# SensorBoard.net
KiCad netlist of a schematic drawn in Altium Designer
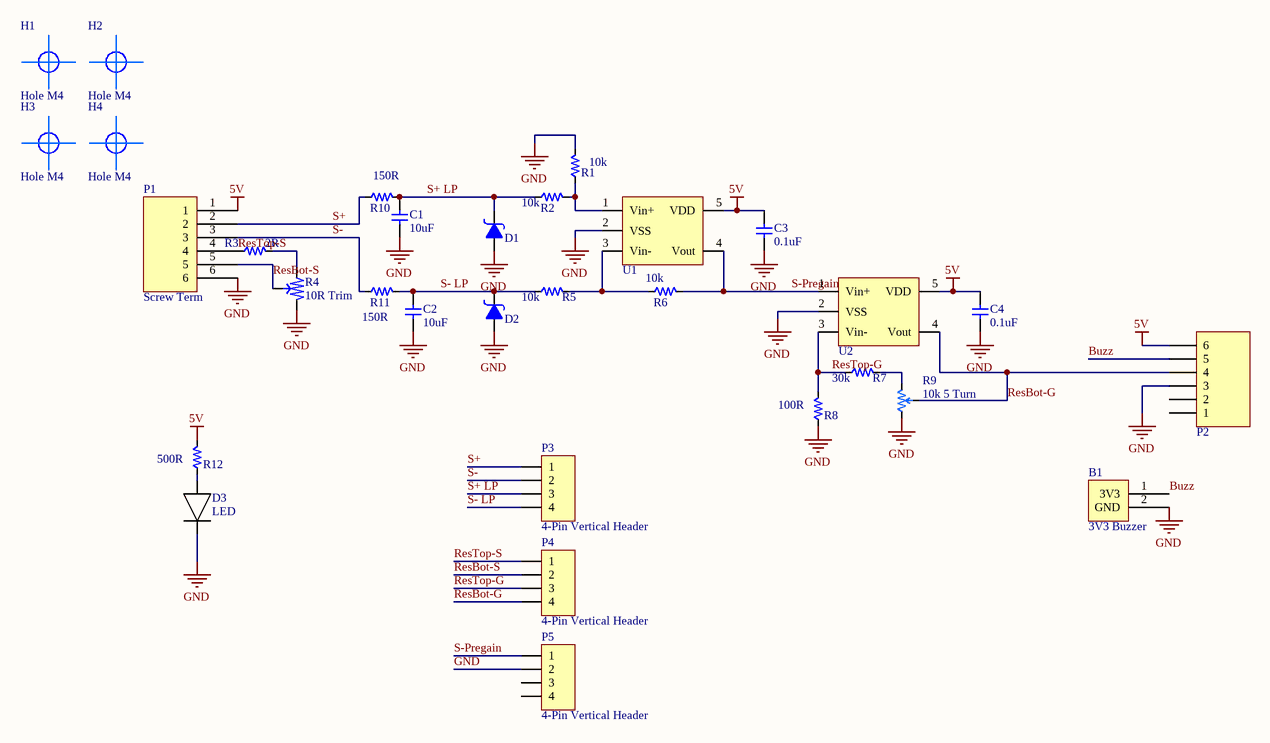
[diagram p0: SensorBoard.SchDoc]

(export (version "E")
  (design (tool "Eeschema 10.0.6"))
  (components
    (comp (ref "B1")
      (value "3V3 Buzzer")
      (footprint "Buzzer_surfacemount")
      (description "AUDIO PIEZO INDICATOR 2-5V TH")
      (libsource (lib "Buzzer_surfacemount") (part "Buzzer_surfacemount"))
    )
    (comp (ref "C1")
      (value "10uF")
      (footprint "PCB_GENERIC_SMD_0603")
      (description "CAP CER 0603 1uF 16V X5R 20%")
      (fields (field (name "TOLERANCE") "20%") (field (name "VOLTAGE") "16V"))
      (libsource (lib "CAP-0603") (part "C060-0001U-00"))
    )
    (comp (ref "C2")
      (value "10uF")
      (footprint "PCB_GENERIC_SMD_0603")
      (description "CAP CER 0603 1uF 16V X5R 20%")
      (fields (field (name "TOLERANCE") "20%") (field (name "VOLTAGE") "16V"))
      (libsource (lib "CAP-0603") (part "C060-0001U-00"))
    )
    (comp (ref "C3")
      (value "0.1uF")
      (footprint "PCB_GENERIC_SMD_0603")
      (description "CAP CER 0603 1uF 16V X5R 20%")
      (fields (field (name "TOLERANCE") "20%") (field (name "VOLTAGE") "16V"))
      (libsource (lib "CAP-0603") (part "C060-0001U-00"))
    )
    (comp (ref "C4")
      (value "0.1uF")
      (footprint "PCB_GENERIC_SMD_0603")
      (description "CAP CER 0603 1uF 16V X5R 20%")
      (fields (field (name "TOLERANCE") "20%") (field (name "VOLTAGE") "16V"))
      (libsource (lib "CAP-0603") (part "C060-0001U-00"))
    )
    (comp (ref "D1")
      (value "ONSEMI_MBRM110LT1G")
      (footprint "ON Semi Schottky Diode - MBRM110LT1G")
      (description "DIODE SCHOTTKY 10V 1A")
      (libsource (lib "ON Semi Schottky Diode") (part "ONSEMI_MBRM110LT1G"))
    )
    (comp (ref "D2")
      (value "ONSEMI_MBRM110LT1G")
      (footprint "ON Semi Schottky Diode - MBRM110LT1G")
      (description "DIODE SCHOTTKY 10V 1A")
      (libsource (lib "ON Semi Schottky Diode") (part "ONSEMI_MBRM110LT1G"))
    )
    (comp (ref "D3")
      (value "LED")
      (footprint "SMD_0603_LED")
      (libsource (lib "0603 LED") (part "SMD_0603_LED"))
    )
    (comp (ref "H1") (value "Hole M4") (footprint "M4_Hole") (libsource (lib "M4") (part "Component_1")))
    (comp (ref "H2") (value "Hole M4") (footprint "M4_Hole") (libsource (lib "M4") (part "Component_1")))
    (comp (ref "H3") (value "Hole M4") (footprint "M4_Hole") (libsource (lib "M4") (part "Component_1")))
    (comp (ref "H4") (value "Hole M4") (footprint "M4_Hole") (libsource (lib "M4") (part "Component_1")))
    (comp (ref "P1")
      (value "Screw Term")
      (footprint "6_Pin_ScrewTerm")
      (description "CONN TERM BLOCK 6POS 5MM BLACK")
      (libsource (lib "6_Pin_ScrewTerm") (part "Component_1"))
    )
    (comp (ref "P2")
      (value "SCH_MLX_MICROFIT_3X2")
      (footprint "PCB_MLX_MICROFIT_3X2")
      (libsource (lib "Molex Microfit 3.0 3x2") (part "SCH_MLX_MICROFIT_3X2"))
    )
    (comp (ref "P3")
      (value "4-Pin Vertical Header")
      (footprint "4-Pin Vertical Header")
      (fields (field (name "MANUFACTURER") "Sullins"))
      (libsource (lib "4 Pin 100 mil Vertical Header - Through Hole") (part "4-Pin Vertical Header"))
    )
    (comp (ref "P4")
      (value "4-Pin Vertical Header")
      (footprint "4-Pin Vertical Header")
      (fields (field (name "MANUFACTURER") "Sullins"))
      (libsource (lib "4 Pin 100 mil Vertical Header - Through Hole") (part "4-Pin Vertical Header"))
    )
    (comp (ref "P5")
      (value "4-Pin Vertical Header")
      (footprint "4-Pin Vertical Header")
      (fields (field (name "MANUFACTURER") "Sullins"))
      (libsource (lib "4 Pin 100 mil Vertical Header - Through Hole") (part "4-Pin Vertical Header"))
    )
    (comp (ref "R1")
      (value "SCH_GENERIC_RESISTOR_0603")
      (footprint "PCB_GENERIC_SMD_0603")
      (description "Generic SMD resistor 0603")
      (fields (field (name "RESISTANCE") "10k"))
      (libsource (lib "Generic 0603 Resistor") (part "SCH_GENERIC_RESISTOR_0603"))
    )
    (comp (ref "R2")
      (value "SCH_GENERIC_RESISTOR_0603")
      (footprint "PCB_GENERIC_SMD_0603")
      (description "Generic SMD resistor 0603")
      (fields (field (name "RESISTANCE") "10k"))
      (libsource (lib "Generic 0603 Resistor") (part "SCH_GENERIC_RESISTOR_0603"))
    )
    (comp (ref "R3")
      (value "SCH_GENERIC_RESISTOR_0603")
      (footprint "PCB_GENERIC_SMD_0603")
      (description "Generic SMD resistor 0603")
      (fields (field (name "RESISTANCE") "2R"))
      (libsource (lib "Generic 0603 Resistor") (part "SCH_GENERIC_RESISTOR_0603"))
    )
    (comp (ref "R4")
      (value "10R Trim")
      (footprint "10ohm1Turn_pot")
      (description "TRIMMER 10 OHM 0.25W SMD")
      (libsource (lib "10ohm1Turn_pot") (part "10ohm1Turn_pot"))
    )
    (comp (ref "R5")
      (value "SCH_GENERIC_RESISTOR_0603")
      (footprint "PCB_GENERIC_SMD_0603")
      (description "Generic SMD resistor 0603")
      (fields (field (name "RESISTANCE") "10k"))
      (libsource (lib "Generic 0603 Resistor") (part "SCH_GENERIC_RESISTOR_0603"))
    )
    (comp (ref "R6")
      (value "SCH_GENERIC_RESISTOR_0603")
      (footprint "PCB_GENERIC_SMD_0603")
      (description "Generic SMD resistor 0603")
      (fields (field (name "RESISTANCE") "10k"))
      (libsource (lib "Generic 0603 Resistor") (part "SCH_GENERIC_RESISTOR_0603"))
    )
    (comp (ref "R7")
      (value "SCH_GENERIC_RESISTOR_0603")
      (footprint "PCB_GENERIC_SMD_0603")
      (description "Generic SMD resistor 0603")
      (fields (field (name "RESISTANCE") "30k"))
      (libsource (lib "Generic 0603 Resistor") (part "SCH_GENERIC_RESISTOR_0603"))
    )
    (comp (ref "R8")
      (value "SCH_GENERIC_RESISTOR_0603")
      (footprint "PCB_GENERIC_SMD_0603")
      (description "Generic SMD resistor 0603")
      (fields (field (name "RESISTANCE") "100R"))
      (libsource (lib "Generic 0603 Resistor") (part "SCH_GENERIC_RESISTOR_0603"))
    )
    (comp (ref "R9")
      (value "10k 5 Turn")
      (footprint "10k5TurnPot")
      (description "TRIMMER 10K OHM 0.25W SMD")
      (libsource (lib "10k5TurnPot") (part "10k 5 Turn"))
    )
    (comp (ref "R10")
      (value "SCH_GENERIC_RESISTOR_0603")
      (footprint "PCB_GENERIC_SMD_0603")
      (description "Generic SMD resistor 0603")
      (fields (field (name "RESISTANCE") "150R"))
      (libsource (lib "Generic 0603 Resistor") (part "SCH_GENERIC_RESISTOR_0603"))
    )
    (comp (ref "R11")
      (value "SCH_GENERIC_RESISTOR_0603")
      (footprint "PCB_GENERIC_SMD_0603")
      (description "Generic SMD resistor 0603")
      (fields (field (name "RESISTANCE") "150R"))
      (libsource (lib "Generic 0603 Resistor") (part "SCH_GENERIC_RESISTOR_0603"))
    )
    (comp (ref "R12")
      (value "SCH_GENERIC_RESISTOR_0603")
      (footprint "PCB_GENERIC_SMD_0603")
      (description "Generic SMD resistor 0603")
      (fields (field (name "RESISTANCE") "500R"))
      (libsource (lib "Generic 0603 Resistor") (part "SCH_GENERIC_RESISTOR_0603"))
    )
    (comp (ref "U1")
      (value "MCP6001U")
      (footprint "MCP6001UT")
      (libsource (lib "Microchip MCP6001UT Op Amp") (part "MCP6001U"))
    )
    (comp (ref "U2")
      (value "MCP6001U")
      (footprint "MCP6001UT")
      (libsource (lib "Microchip MCP6001UT Op Amp") (part "MCP6001U"))
    )
  )
  (nets
    (net (code "1") (name "/Buzz") (class "Default")
      (node (ref "B1") (pin "1") (pinfunction "3V3_1") (pintype "passive"))
      (node (ref "P2") (pin "5") (pinfunction "5_5") (pintype "passive"))
    )
    (net (code "2") (name "/ResBot-G") (class "Default")
      (node (ref "P2") (pin "4") (pinfunction "4_4") (pintype "passive"))
      (node (ref "P4") (pin "4") (pinfunction "4_4") (pintype "passive"))
      (node (ref "R9") (pin "2") (pinfunction "2_2") (pintype "passive"))
      (node (ref "U2") (pin "4") (pinfunction "Vout_4") (pintype "passive"))
    )
    (net (code "3") (name "/ResBot-S") (class "Default")
      (node (ref "P1") (pin "5") (pinfunction "5_5") (pintype "passive"))
      (node (ref "P4") (pin "2") (pinfunction "2_2") (pintype "passive"))
      (node (ref "R4") (pin "2") (pinfunction "2_2") (pintype "passive"))
    )
    (net (code "4") (name "/ResTop-G") (class "Default")
      (node (ref "P4") (pin "3") (pinfunction "3_3") (pintype "passive"))
      (node (ref "R7") (pin "1") (pinfunction "1_1") (pintype "passive"))
      (node (ref "R8") (pin "2") (pinfunction "2_2") (pintype "passive"))
      (node (ref "U2") (pin "3") (pinfunction "Vin-_3") (pintype "passive"))
    )
    (net (code "5") (name "/ResTop-S") (class "Default")
      (node (ref "P1") (pin "4") (pinfunction "4_4") (pintype "passive"))
      (node (ref "P4") (pin "1") (pinfunction "1_1") (pintype "passive"))
      (node (ref "R3") (pin "1") (pinfunction "1_1") (pintype "passive"))
    )
    (net (code "6") (name "/S+") (class "Default")
      (node (ref "P1") (pin "2") (pinfunction "2_2") (pintype "passive"))
      (node (ref "P3") (pin "1") (pinfunction "1_1") (pintype "passive"))
      (node (ref "R10") (pin "1") (pinfunction "1_1") (pintype "passive"))
    )
    (net (code "7") (name "/S+ LP") (class "Default")
      (node (ref "C1") (pin "2") (pinfunction "2_2") (pintype "passive"))
      (node (ref "D1") (pin "1") (pinfunction "1_1") (pintype "passive"))
      (node (ref "P3") (pin "3") (pinfunction "3_3") (pintype "passive"))
      (node (ref "R10") (pin "2") (pinfunction "2_2") (pintype "passive"))
      (node (ref "R2") (pin "1") (pinfunction "1_1") (pintype "passive"))
    )
    (net (code "8") (name "/S-") (class "Default")
      (node (ref "P1") (pin "3") (pinfunction "3_3") (pintype "passive"))
      (node (ref "P3") (pin "2") (pinfunction "2_2") (pintype "passive"))
      (node (ref "R11") (pin "1") (pinfunction "1_1") (pintype "passive"))
    )
    (net (code "9") (name "/S- LP") (class "Default")
      (node (ref "C2") (pin "2") (pinfunction "2_2") (pintype "passive"))
      (node (ref "D2") (pin "1") (pinfunction "1_1") (pintype "passive"))
      (node (ref "P3") (pin "4") (pinfunction "4_4") (pintype "passive"))
      (node (ref "R11") (pin "2") (pinfunction "2_2") (pintype "passive"))
      (node (ref "R5") (pin "1") (pinfunction "1_1") (pintype "passive"))
    )
    (net (code "10") (name "/S-Pregain") (class "Default")
      (node (ref "P5") (pin "1") (pinfunction "1_1") (pintype "passive"))
      (node (ref "R6") (pin "2") (pinfunction "2_2") (pintype "passive"))
      (node (ref "U1") (pin "4") (pinfunction "Vout_4") (pintype "passive"))
      (node (ref "U2") (pin "1") (pinfunction "Vin+_1") (pintype "passive"))
    )
    (net (code "11") (name "5V") (class "Default")
      (node (ref "C3") (pin "2") (pinfunction "2_2") (pintype "passive"))
      (node (ref "C4") (pin "2") (pinfunction "2_2") (pintype "passive"))
      (node (ref "P1") (pin "1") (pinfunction "1_1") (pintype "passive"))
      (node (ref "P2") (pin "6") (pinfunction "6_6") (pintype "passive"))
      (node (ref "R12") (pin "2") (pinfunction "2_2") (pintype "passive"))
      (node (ref "U1") (pin "5") (pinfunction "VDD_5") (pintype "passive"))
      (node (ref "U2") (pin "5") (pinfunction "VDD_5") (pintype "passive"))
    )
    (net (code "12") (name "GND") (class "Default")
      (node (ref "B1") (pin "2") (pinfunction "GND_2") (pintype "passive"))
      (node (ref "C1") (pin "1") (pinfunction "1_1") (pintype "passive"))
      (node (ref "C2") (pin "1") (pinfunction "1_1") (pintype "passive"))
      (node (ref "C3") (pin "1") (pinfunction "1_1") (pintype "passive"))
      (node (ref "C4") (pin "1") (pinfunction "1_1") (pintype "passive"))
      (node (ref "D1") (pin "2") (pinfunction "2_2") (pintype "passive"))
      (node (ref "D2") (pin "2") (pinfunction "2_2") (pintype "passive"))
      (node (ref "D3") (pin "2") (pinfunction "2_2") (pintype "passive"))
      (node (ref "P1") (pin "6") (pinfunction "6_6") (pintype "passive"))
      (node (ref "P2") (pin "3") (pinfunction "3_3") (pintype "passive"))
      (node (ref "P5") (pin "2") (pinfunction "2_2") (pintype "passive"))
      (node (ref "R1") (pin "2") (pinfunction "2_2") (pintype "passive"))
      (node (ref "R4") (pin "1") (pinfunction "1_1") (pintype "passive"))
      (node (ref "R8") (pin "1") (pinfunction "1_1") (pintype "passive"))
      (node (ref "R9") (pin "3") (pinfunction "3_3") (pintype "passive"))
      (node (ref "U1") (pin "2") (pinfunction "VSS_2") (pintype "passive"))
      (node (ref "U2") (pin "2") (pinfunction "VSS_2") (pintype "passive"))
    )
    (net (code "13") (name "Net-(D3-Pad1)") (class "Default")
      (node (ref "D3") (pin "1") (pinfunction "1_1") (pintype "passive"))
      (node (ref "R12") (pin "1") (pinfunction "1_1") (pintype "passive"))
    )
    (net (code "14") (name "Net-(R3-Pad2)") (class "Default")
      (node (ref "R3") (pin "2") (pinfunction "2_2") (pintype "passive"))
      (node (ref "R4") (pin "3") (pinfunction "3_3") (pintype "passive"))
    )
    (net (code "15") (name "Net-(R7-Pad2)") (class "Default")
      (node (ref "R7") (pin "2") (pinfunction "2_2") (pintype "passive"))
      (node (ref "R9") (pin "1") (pinfunction "1_1") (pintype "passive"))
    )
    (net (code "16") (name "Net-(U1-Vin+)") (class "Default")
      (node (ref "R1") (pin "1") (pinfunction "1_1") (pintype "passive"))
      (node (ref "R2") (pin "2") (pinfunction "2_2") (pintype "passive"))
      (node (ref "U1") (pin "1") (pinfunction "Vin+_1") (pintype "passive"))
    )
    (net (code "17") (name "Net-(U1-Vin-)") (class "Default")
      (node (ref "R5") (pin "2") (pinfunction "2_2") (pintype "passive"))
      (node (ref "R6") (pin "1") (pinfunction "1_1") (pintype "passive"))
      (node (ref "U1") (pin "3") (pinfunction "Vin-_3") (pintype "passive"))
    )
    (net (code "18") (name "unconnected-(P2-Pad1)") (class "Default")
      (node (ref "P2") (pin "1") (pinfunction "1_1") (pintype "passive"))
    )
    (net (code "19") (name "unconnected-(P2-Pad2)") (class "Default")
      (node (ref "P2") (pin "2") (pinfunction "2_2") (pintype "passive"))
    )
    (net (code "20") (name "unconnected-(P5-Pad3)") (class "Default")
      (node (ref "P5") (pin "3") (pinfunction "3_3") (pintype "passive"))
    )
    (net (code "21") (name "unconnected-(P5-Pad4)") (class "Default")
      (node (ref "P5") (pin "4") (pinfunction "4_4") (pintype "passive"))
    )
  )
)
